# WayHugeAngryTroll.net
KiCad netlist of a schematic drawn in EAGLE
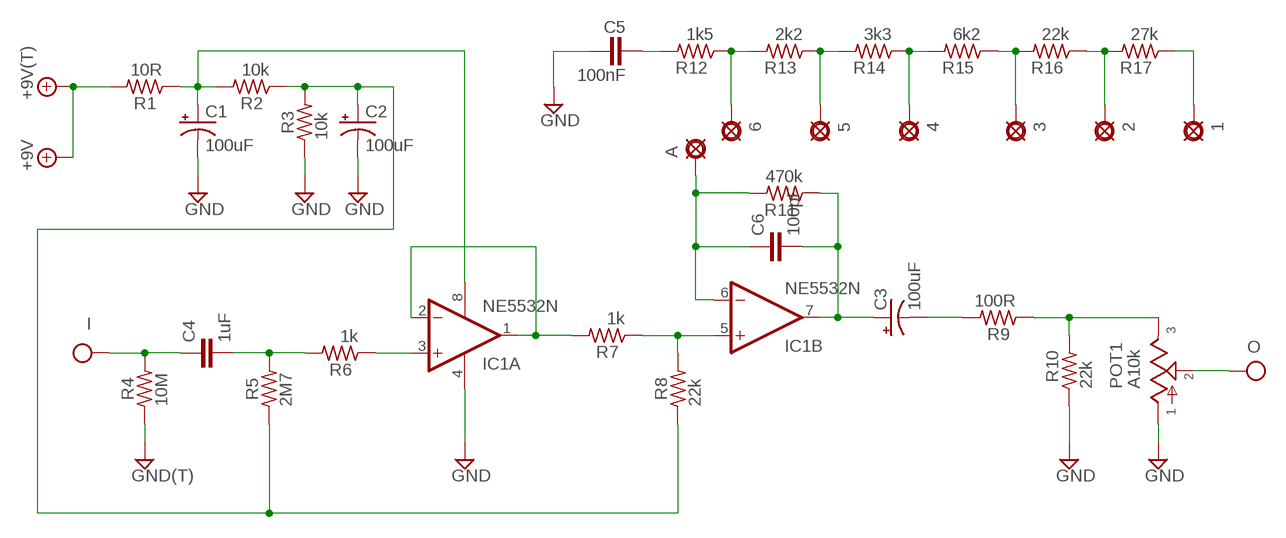
[diagram p0: schematic, sheet 1]

(export (version "E")
  (design (tool "Eeschema 10.0.6"))
  (components
    (comp (ref "+9")
      (value "+9V(T)")
      (footprint "eagle-import:SQUARE")
      (libsource (lib "eagle-import") (part "+9V(T)"))
    )
    (comp (ref "1")
      (value "PAD8")
      (footprint "eagle-import:OCTOGON")
      (libsource (lib "eagle-import") (part "PAD8"))
    )
    (comp (ref "2")
      (value "PAD8")
      (footprint "eagle-import:OCTOGON")
      (libsource (lib "eagle-import") (part "PAD8"))
    )
    (comp (ref "3")
      (value "PAD8")
      (footprint "eagle-import:OCTOGON")
      (libsource (lib "eagle-import") (part "PAD8"))
    )
    (comp (ref "4")
      (value "PAD8")
      (footprint "eagle-import:OCTOGON")
      (libsource (lib "eagle-import") (part "PAD8"))
    )
    (comp (ref "5")
      (value "PAD8")
      (footprint "eagle-import:OCTOGON")
      (libsource (lib "eagle-import") (part "PAD8"))
    )
    (comp (ref "6")
      (value "PAD8")
      (footprint "eagle-import:OCTOGON")
      (libsource (lib "eagle-import") (part "PAD8"))
    )
    (comp (ref "A")
      (value "PAD8")
      (footprint "eagle-import:OCTOGON")
      (libsource (lib "eagle-import") (part "PAD8"))
    )
    (comp (ref "C1")
      (value "100uF")
      (footprint "eagle-import:063_025")
      (libsource (lib "eagle-import") (part "0631"))
    )
    (comp (ref "C2")
      (value "100uF")
      (footprint "eagle-import:063_025")
      (libsource (lib "eagle-import") (part "0631"))
    )
    (comp (ref "C3")
      (value "100uF")
      (footprint "eagle-import:063_025")
      (libsource (lib "eagle-import") (part "0631"))
    )
    (comp (ref "C4")
      (value "1uF")
      (footprint "eagle-import:080X050")
      (libsource (lib "eagle-import") (part "080X0502"))
    )
    (comp (ref "C5")
      (value "100nF")
      (footprint "eagle-import:072X035")
      (libsource (lib "eagle-import") (part "072X0352"))
    )
    (comp (ref "C6")
      (value "100pF")
      (footprint "eagle-import:050X030_025")
      (libsource (lib "eagle-import") (part "050X030_0251"))
    )
    (comp (ref "G")
      (value "GND(T)")
      (footprint "eagle-import:SQUARE")
      (libsource (lib "eagle-import") (part "GND(T)"))
    )
    (comp (ref "I")
      (value "IN(T)")
      (footprint "eagle-import:SQUARE")
      (libsource (lib "eagle-import") (part "IN(T)"))
    )
    (comp (ref "IC1")
      (value "NE5532N")
      (footprint "eagle-import:DIL08")
      (libsource (lib "eagle-import") (part "NE5532N"))
    )
    (comp (ref "O")
      (value "OUT(T)")
      (footprint "eagle-import:SQUARE")
      (libsource (lib "eagle-import") (part "OUT(T)"))
    )
    (comp (ref "POT1")
      (value "A10k")
      (footprint "eagle-import:16MM-ROUND")
      (libsource (lib "eagle-import") (part "POTR"))
    )
    (comp (ref "R1")
      (value "10R")
      (footprint "eagle-import:R0207_3")
      (libsource (lib "eagle-import") (part "6MM.3"))
    )
    (comp (ref "R2")
      (value "10k")
      (footprint "eagle-import:R0207_3")
      (libsource (lib "eagle-import") (part "6MM.3"))
    )
    (comp (ref "R3")
      (value "10k")
      (footprint "eagle-import:R0207_3")
      (libsource (lib "eagle-import") (part "6MM.3"))
    )
    (comp (ref "R4")
      (value "10M")
      (footprint "eagle-import:R0207_3")
      (libsource (lib "eagle-import") (part "6MM.3"))
    )
    (comp (ref "R5")
      (value "2M7")
      (footprint "eagle-import:R0207_3")
      (libsource (lib "eagle-import") (part "6MM.3"))
    )
    (comp (ref "R6")
      (value "1k")
      (footprint "eagle-import:R0207_3")
      (libsource (lib "eagle-import") (part "6MM.3"))
    )
    (comp (ref "R7")
      (value "1k")
      (footprint "eagle-import:R0207_3")
      (libsource (lib "eagle-import") (part "6MM.3"))
    )
    (comp (ref "R8")
      (value "22k")
      (footprint "eagle-import:R0207_3")
      (libsource (lib "eagle-import") (part "6MM.3"))
    )
    (comp (ref "R9")
      (value "100R")
      (footprint "eagle-import:R0207_3")
      (libsource (lib "eagle-import") (part "6MM.3"))
    )
    (comp (ref "R10")
      (value "22k")
      (footprint "eagle-import:R0207_3")
      (libsource (lib "eagle-import") (part "6MM.3"))
    )
    (comp (ref "R11")
      (value "470k")
      (footprint "eagle-import:R0207_3")
      (libsource (lib "eagle-import") (part "6MM.3"))
    )
    (comp (ref "R12")
      (value "1k5")
      (footprint "eagle-import:R0207_3")
      (libsource (lib "eagle-import") (part "6MM.3"))
    )
    (comp (ref "R13")
      (value "2k2")
      (footprint "eagle-import:R0207_3")
      (libsource (lib "eagle-import") (part "6MM.3"))
    )
    (comp (ref "R14")
      (value "3k3")
      (footprint "eagle-import:R0207_3")
      (libsource (lib "eagle-import") (part "6MM.3"))
    )
    (comp (ref "R15")
      (value "6k2")
      (footprint "eagle-import:R0207_3")
      (libsource (lib "eagle-import") (part "6MM.3"))
    )
    (comp (ref "R16")
      (value "22k")
      (footprint "eagle-import:R0207_3")
      (libsource (lib "eagle-import") (part "6MM.3"))
    )
    (comp (ref "R17")
      (value "27k")
      (footprint "eagle-import:R0207_3")
      (libsource (lib "eagle-import") (part "6MM.3"))
    )
  )
  (nets
    (net (code "1") (name "+9V") (class "Default")
      (node (ref "+9") (pin "1") (pinfunction "+9V_1") (pintype "power_in"))
      (node (ref "R1") (pin "2") (pinfunction "2_2") (pintype "passive"))
    )
    (net (code "2") (name "GND") (class "Default")
      (node (ref "C1") (pin "-") (pinfunction "-_-") (pintype "passive"))
      (node (ref "C2") (pin "-") (pinfunction "-_-") (pintype "passive"))
      (node (ref "C5") (pin "1") (pinfunction "1_1") (pintype "passive"))
      (node (ref "G") (pin "1") (pinfunction "GND_1") (pintype "power_in"))
      (node (ref "IC1") (pin "4") (pinfunction "V-_4") (pintype "power_in"))
      (node (ref "POT1") (pin "1") (pinfunction "1_1") (pintype "passive"))
      (node (ref "R10") (pin "1") (pinfunction "1_1") (pintype "passive"))
      (node (ref "R3") (pin "1") (pinfunction "1_1") (pintype "passive"))
      (node (ref "R4") (pin "1") (pinfunction "1_1") (pintype "passive"))
    )
    (net (code "3") (name "IN(T)") (class "Default")
      (node (ref "C4") (pin "1") (pinfunction "1_1") (pintype "passive"))
      (node (ref "I") (pin "1") (pinfunction "IN_1") (pintype "power_in"))
      (node (ref "R4") (pin "2") (pinfunction "2_2") (pintype "passive"))
    )
    (net (code "4") (name "Net-(1-PAD)") (class "Default")
      (node (ref "1") (pin "1") (pinfunction "PAD_1") (pintype "passive"))
      (node (ref "R17") (pin "1") (pinfunction "1_1") (pintype "passive"))
    )
    (net (code "5") (name "Net-(2-PAD)") (class "Default")
      (node (ref "2") (pin "1") (pinfunction "PAD_1") (pintype "passive"))
      (node (ref "R16") (pin "1") (pinfunction "1_1") (pintype "passive"))
      (node (ref "R17") (pin "2") (pinfunction "2_2") (pintype "passive"))
    )
    (net (code "6") (name "Net-(3-PAD)") (class "Default")
      (node (ref "3") (pin "1") (pinfunction "PAD_1") (pintype "passive"))
      (node (ref "R15") (pin "1") (pinfunction "1_1") (pintype "passive"))
      (node (ref "R16") (pin "2") (pinfunction "2_2") (pintype "passive"))
    )
    (net (code "7") (name "Net-(4-PAD)") (class "Default")
      (node (ref "4") (pin "1") (pinfunction "PAD_1") (pintype "passive"))
      (node (ref "R14") (pin "1") (pinfunction "1_1") (pintype "passive"))
      (node (ref "R15") (pin "2") (pinfunction "2_2") (pintype "passive"))
    )
    (net (code "8") (name "Net-(5-PAD)") (class "Default")
      (node (ref "5") (pin "1") (pinfunction "PAD_1") (pintype "passive"))
      (node (ref "R13") (pin "1") (pinfunction "1_1") (pintype "passive"))
      (node (ref "R14") (pin "2") (pinfunction "2_2") (pintype "passive"))
    )
    (net (code "9") (name "Net-(6-PAD)") (class "Default")
      (node (ref "6") (pin "1") (pinfunction "PAD_1") (pintype "passive"))
      (node (ref "R12") (pin "1") (pinfunction "1_1") (pintype "passive"))
      (node (ref "R13") (pin "2") (pinfunction "2_2") (pintype "passive"))
    )
    (net (code "10") (name "Net-(A-PAD)") (class "Default")
      (node (ref "A") (pin "1") (pinfunction "PAD_1") (pintype "passive"))
      (node (ref "C6") (pin "1") (pinfunction "1_1") (pintype "passive"))
      (node (ref "IC1") (pin "6") (pinfunction "-IN_6") (pintype "input"))
      (node (ref "R11") (pin "2") (pinfunction "2_2") (pintype "passive"))
    )
    (net (code "11") (name "Net-(C2-Pad+)") (class "Default")
      (node (ref "C2") (pin "+") (pinfunction "+_+") (pintype "passive"))
      (node (ref "R2") (pin "1") (pinfunction "1_1") (pintype "passive"))
      (node (ref "R3") (pin "2") (pinfunction "2_2") (pintype "passive"))
      (node (ref "R5") (pin "1") (pinfunction "1_1") (pintype "passive"))
      (node (ref "R8") (pin "1") (pinfunction "1_1") (pintype "passive"))
    )
    (net (code "12") (name "Net-(C3-Pad-)") (class "Default")
      (node (ref "C3") (pin "-") (pinfunction "-_-") (pintype "passive"))
      (node (ref "R9") (pin "2") (pinfunction "2_2") (pintype "passive"))
    )
    (net (code "13") (name "Net-(C4-Pad2)") (class "Default")
      (node (ref "C4") (pin "2") (pinfunction "2_2") (pintype "passive"))
      (node (ref "R5") (pin "2") (pinfunction "2_2") (pintype "passive"))
      (node (ref "R6") (pin "2") (pinfunction "2_2") (pintype "passive"))
    )
    (net (code "14") (name "Net-(C5-Pad2)") (class "Default")
      (node (ref "C5") (pin "2") (pinfunction "2_2") (pintype "passive"))
      (node (ref "R12") (pin "2") (pinfunction "2_2") (pintype "passive"))
    )
    (net (code "15") (name "Net-(IC1A-+IN)") (class "Default")
      (node (ref "IC1") (pin "3") (pinfunction "+IN_3") (pintype "input"))
      (node (ref "R6") (pin "1") (pinfunction "1_1") (pintype "passive"))
    )
    (net (code "16") (name "Net-(IC1A--IN)") (class "Default")
      (node (ref "IC1") (pin "1") (pinfunction "OUT_1") (pintype "output"))
      (node (ref "IC1") (pin "2") (pinfunction "-IN_2") (pintype "input"))
      (node (ref "R7") (pin "2") (pinfunction "2_2") (pintype "passive"))
    )
    (net (code "17") (name "Net-(IC1B-+IN)") (class "Default")
      (node (ref "IC1") (pin "5") (pinfunction "+IN_5") (pintype "input"))
      (node (ref "R7") (pin "1") (pinfunction "1_1") (pintype "passive"))
      (node (ref "R8") (pin "2") (pinfunction "2_2") (pintype "passive"))
    )
    (net (code "18") (name "Net-(IC1B-OUT)") (class "Default")
      (node (ref "C3") (pin "+") (pinfunction "+_+") (pintype "passive"))
      (node (ref "C6") (pin "2") (pinfunction "2_2") (pintype "passive"))
      (node (ref "IC1") (pin "7") (pinfunction "OUT_7") (pintype "output"))
      (node (ref "R11") (pin "1") (pinfunction "1_1") (pintype "passive"))
    )
    (net (code "19") (name "Net-(IC1C-V+)") (class "Default")
      (node (ref "C1") (pin "+") (pinfunction "+_+") (pintype "passive"))
      (node (ref "IC1") (pin "8") (pinfunction "V+_8") (pintype "power_in"))
      (node (ref "R1") (pin "1") (pinfunction "1_1") (pintype "passive"))
      (node (ref "R2") (pin "2") (pinfunction "2_2") (pintype "passive"))
    )
    (net (code "20") (name "Net-(POT1-Pad3)") (class "Default")
      (node (ref "POT1") (pin "3") (pinfunction "3_3") (pintype "passive"))
      (node (ref "R10") (pin "2") (pinfunction "2_2") (pintype "passive"))
      (node (ref "R9") (pin "1") (pinfunction "1_1") (pintype "passive"))
    )
    (net (code "21") (name "OUT(T)") (class "Default")
      (node (ref "O") (pin "1") (pinfunction "OUT_1") (pintype "power_in"))
      (node (ref "POT1") (pin "2") (pinfunction "2_2") (pintype "passive"))
    )
  )
)
